# MainBoard.net
KiCad netlist of a schematic drawn in Altium Designer
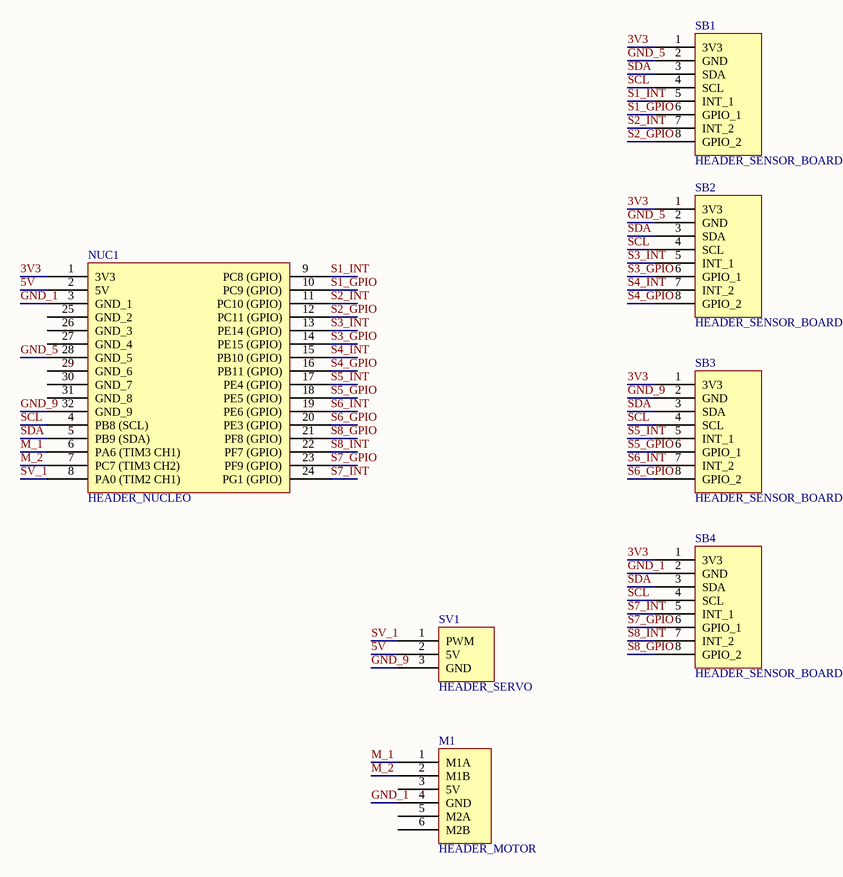
[diagram p0: MainBoard.SchDoc]

(export (version "E")
  (design (tool "Eeschema 10.0.6"))
  (components
    (comp (ref "M1")
      (value "HEADER_MOTOR")
      (footprint "HEADER_MOTOR")
      (libsource (lib "Components") (part "HEADER_MOTOR"))
    )
    (comp (ref "NUC1")
      (value "HEADER_NUCLEO")
      (footprint "HEADER_NUCLEO")
      (libsource (lib "Components") (part "HEADER_NUCLEO"))
    )
    (comp (ref "SB1")
      (value "HEADER_SENSOR_BOARD")
      (footprint "HEADER_SENSOR_BOARD")
      (description "Sensor Board header")
      (libsource (lib "Components") (part "HEADER_SENSOR_BOARD"))
    )
    (comp (ref "SB2")
      (value "HEADER_SENSOR_BOARD")
      (footprint "HEADER_SENSOR_BOARD")
      (description "Sensor Board header")
      (libsource (lib "Components") (part "HEADER_SENSOR_BOARD"))
    )
    (comp (ref "SB3")
      (value "HEADER_SENSOR_BOARD")
      (footprint "HEADER_SENSOR_BOARD")
      (description "Sensor Board header")
      (libsource (lib "Components") (part "HEADER_SENSOR_BOARD"))
    )
    (comp (ref "SB4")
      (value "HEADER_SENSOR_BOARD")
      (footprint "HEADER_SENSOR_BOARD")
      (description "Sensor Board header")
      (libsource (lib "Components") (part "HEADER_SENSOR_BOARD"))
    )
    (comp (ref "SV1")
      (value "HEADER_SERVO")
      (footprint "HEADER_3PIN")
      (libsource (lib "Components") (part "HEADER_SERVO"))
    )
  )
  (nets
    (net (code "1") (name "/3V3") (class "Default")
      (node (ref "NUC1") (pin "1") (pinfunction "3V3_1") (pintype "passive"))
      (node (ref "SB1") (pin "1") (pinfunction "3V3_1") (pintype "passive"))
      (node (ref "SB2") (pin "1") (pinfunction "3V3_1") (pintype "passive"))
      (node (ref "SB3") (pin "1") (pinfunction "3V3_1") (pintype "passive"))
      (node (ref "SB4") (pin "1") (pinfunction "3V3_1") (pintype "passive"))
    )
    (net (code "2") (name "/5V") (class "Default")
      (node (ref "NUC1") (pin "2") (pinfunction "5V_2") (pintype "passive"))
      (node (ref "SV1") (pin "2") (pinfunction "5V_2") (pintype "passive"))
    )
    (net (code "3") (name "/GND_1") (class "Default")
      (node (ref "M1") (pin "4") (pinfunction "GND_4") (pintype "passive"))
      (node (ref "NUC1") (pin "3") (pinfunction "GND_1_3") (pintype "passive"))
      (node (ref "SB4") (pin "2") (pinfunction "GND_2") (pintype "passive"))
    )
    (net (code "4") (name "/GND_5") (class "Default")
      (node (ref "NUC1") (pin "28") (pinfunction "GND_5_28") (pintype "passive"))
      (node (ref "SB1") (pin "2") (pinfunction "GND_2") (pintype "passive"))
      (node (ref "SB2") (pin "2") (pinfunction "GND_2") (pintype "passive"))
    )
    (net (code "5") (name "/GND_9") (class "Default")
      (node (ref "NUC1") (pin "32") (pinfunction "GND_9_32") (pintype "passive"))
      (node (ref "SB3") (pin "2") (pinfunction "GND_2") (pintype "passive"))
      (node (ref "SV1") (pin "3") (pinfunction "GND_3") (pintype "passive"))
    )
    (net (code "6") (name "/M_1") (class "Default")
      (node (ref "M1") (pin "1") (pinfunction "M1A_1") (pintype "passive"))
      (node (ref "NUC1") (pin "6") (pinfunction "PA6_(TIM3_CH1)_6") (pintype "passive"))
    )
    (net (code "7") (name "/M_2") (class "Default")
      (node (ref "M1") (pin "2") (pinfunction "M1B_2") (pintype "passive"))
      (node (ref "NUC1") (pin "7") (pinfunction "PC7_(TIM3_CH2)_7") (pintype "passive"))
    )
    (net (code "8") (name "/S1_GPIO") (class "Default")
      (node (ref "NUC1") (pin "10") (pinfunction "PC9_(GPIO)_10") (pintype "passive"))
      (node (ref "SB1") (pin "6") (pinfunction "GPIO_1_6") (pintype "passive"))
    )
    (net (code "9") (name "/S1_INT") (class "Default")
      (node (ref "NUC1") (pin "9") (pinfunction "PC8_(GPIO)_9") (pintype "passive"))
      (node (ref "SB1") (pin "5") (pinfunction "INT_1_5") (pintype "passive"))
    )
    (net (code "10") (name "/S2_GPIO") (class "Default")
      (node (ref "NUC1") (pin "12") (pinfunction "PC11_(GPIO)_12") (pintype "passive"))
      (node (ref "SB1") (pin "8") (pinfunction "GPIO_2_8") (pintype "passive"))
    )
    (net (code "11") (name "/S2_INT") (class "Default")
      (node (ref "NUC1") (pin "11") (pinfunction "PC10_(GPIO)_11") (pintype "passive"))
      (node (ref "SB1") (pin "7") (pinfunction "INT_2_7") (pintype "passive"))
    )
    (net (code "12") (name "/S3_GPIO") (class "Default")
      (node (ref "NUC1") (pin "14") (pinfunction "PE15_(GPIO)_14") (pintype "passive"))
      (node (ref "SB2") (pin "6") (pinfunction "GPIO_1_6") (pintype "passive"))
    )
    (net (code "13") (name "/S3_INT") (class "Default")
      (node (ref "NUC1") (pin "13") (pinfunction "PE14_(GPIO)_13") (pintype "passive"))
      (node (ref "SB2") (pin "5") (pinfunction "INT_1_5") (pintype "passive"))
    )
    (net (code "14") (name "/S4_GPIO") (class "Default")
      (node (ref "NUC1") (pin "16") (pinfunction "PB11_(GPIO)_16") (pintype "passive"))
      (node (ref "SB2") (pin "8") (pinfunction "GPIO_2_8") (pintype "passive"))
    )
    (net (code "15") (name "/S4_INT") (class "Default")
      (node (ref "NUC1") (pin "15") (pinfunction "PB10_(GPIO)_15") (pintype "passive"))
      (node (ref "SB2") (pin "7") (pinfunction "INT_2_7") (pintype "passive"))
    )
    (net (code "16") (name "/S5_GPIO") (class "Default")
      (node (ref "NUC1") (pin "18") (pinfunction "PE5_(GPIO)_18") (pintype "passive"))
      (node (ref "SB3") (pin "6") (pinfunction "GPIO_1_6") (pintype "passive"))
    )
    (net (code "17") (name "/S5_INT") (class "Default")
      (node (ref "NUC1") (pin "17") (pinfunction "PE4_(GPIO)_17") (pintype "passive"))
      (node (ref "SB3") (pin "5") (pinfunction "INT_1_5") (pintype "passive"))
    )
    (net (code "18") (name "/S6_GPIO") (class "Default")
      (node (ref "NUC1") (pin "20") (pinfunction "PE3_(GPIO)_20") (pintype "passive"))
      (node (ref "SB3") (pin "8") (pinfunction "GPIO_2_8") (pintype "passive"))
    )
    (net (code "19") (name "/S6_INT") (class "Default")
      (node (ref "NUC1") (pin "19") (pinfunction "PE6_(GPIO)_19") (pintype "passive"))
      (node (ref "SB3") (pin "7") (pinfunction "INT_2_7") (pintype "passive"))
    )
    (net (code "20") (name "/S7_GPIO") (class "Default")
      (node (ref "NUC1") (pin "23") (pinfunction "PF9_(GPIO)_23") (pintype "passive"))
      (node (ref "SB4") (pin "6") (pinfunction "GPIO_1_6") (pintype "passive"))
    )
    (net (code "21") (name "/S7_INT") (class "Default")
      (node (ref "NUC1") (pin "24") (pinfunction "PG1_(GPIO)_24") (pintype "passive"))
      (node (ref "SB4") (pin "5") (pinfunction "INT_1_5") (pintype "passive"))
    )
    (net (code "22") (name "/S8_GPIO") (class "Default")
      (node (ref "NUC1") (pin "21") (pinfunction "PF8_(GPIO)_21") (pintype "passive"))
      (node (ref "SB4") (pin "8") (pinfunction "GPIO_2_8") (pintype "passive"))
    )
    (net (code "23") (name "/S8_INT") (class "Default")
      (node (ref "NUC1") (pin "22") (pinfunction "PF7_(GPIO)_22") (pintype "passive"))
      (node (ref "SB4") (pin "7") (pinfunction "INT_2_7") (pintype "passive"))
    )
    (net (code "24") (name "/SCL") (class "Default")
      (node (ref "NUC1") (pin "4") (pinfunction "PB8_(SCL)_4") (pintype "passive"))
      (node (ref "SB1") (pin "4") (pinfunction "SCL_4") (pintype "passive"))
      (node (ref "SB2") (pin "4") (pinfunction "SCL_4") (pintype "passive"))
      (node (ref "SB3") (pin "4") (pinfunction "SCL_4") (pintype "passive"))
      (node (ref "SB4") (pin "4") (pinfunction "SCL_4") (pintype "passive"))
    )
    (net (code "25") (name "/SDA") (class "Default")
      (node (ref "NUC1") (pin "5") (pinfunction "PB9_(SDA)_5") (pintype "passive"))
      (node (ref "SB1") (pin "3") (pinfunction "SDA_3") (pintype "passive"))
      (node (ref "SB2") (pin "3") (pinfunction "SDA_3") (pintype "passive"))
      (node (ref "SB3") (pin "3") (pinfunction "SDA_3") (pintype "passive"))
      (node (ref "SB4") (pin "3") (pinfunction "SDA_3") (pintype "passive"))
    )
    (net (code "26") (name "/SV_1") (class "Default")
      (node (ref "NUC1") (pin "8") (pinfunction "PA0_(TIM2_CH1)_8") (pintype "passive"))
      (node (ref "SV1") (pin "1") (pinfunction "PWM_1") (pintype "passive"))
    )
    (net (code "27") (name "unconnected-(M1-5V-Pad3)") (class "Default")
      (node (ref "M1") (pin "3") (pinfunction "5V_3") (pintype "passive"))
    )
    (net (code "28") (name "unconnected-(M1-M2A-Pad5)") (class "Default")
      (node (ref "M1") (pin "5") (pinfunction "M2A_5") (pintype "passive"))
    )
    (net (code "29") (name "unconnected-(M1-M2B-Pad6)") (class "Default")
      (node (ref "M1") (pin "6") (pinfunction "M2B_6") (pintype "passive"))
    )
    (net (code "30") (name "unconnected-(NUC1-GND_2-Pad25)") (class "Default")
      (node (ref "NUC1") (pin "25") (pinfunction "GND_2_25") (pintype "passive"))
    )
    (net (code "31") (name "unconnected-(NUC1-GND_3-Pad26)") (class "Default")
      (node (ref "NUC1") (pin "26") (pinfunction "GND_3_26") (pintype "passive"))
    )
    (net (code "32") (name "unconnected-(NUC1-GND_4-Pad27)") (class "Default")
      (node (ref "NUC1") (pin "27") (pinfunction "GND_4_27") (pintype "passive"))
    )
    (net (code "33") (name "unconnected-(NUC1-GND_6-Pad29)") (class "Default")
      (node (ref "NUC1") (pin "29") (pinfunction "GND_6_29") (pintype "passive"))
    )
    (net (code "34") (name "unconnected-(NUC1-GND_7-Pad30)") (class "Default")
      (node (ref "NUC1") (pin "30") (pinfunction "GND_7_30") (pintype "passive"))
    )
    (net (code "35") (name "unconnected-(NUC1-GND_8-Pad31)") (class "Default")
      (node (ref "NUC1") (pin "31") (pinfunction "GND_8_31") (pintype "passive"))
    )
  )
)
